# v0_1.net
KiCad netlist of a schematic drawn in EAGLE
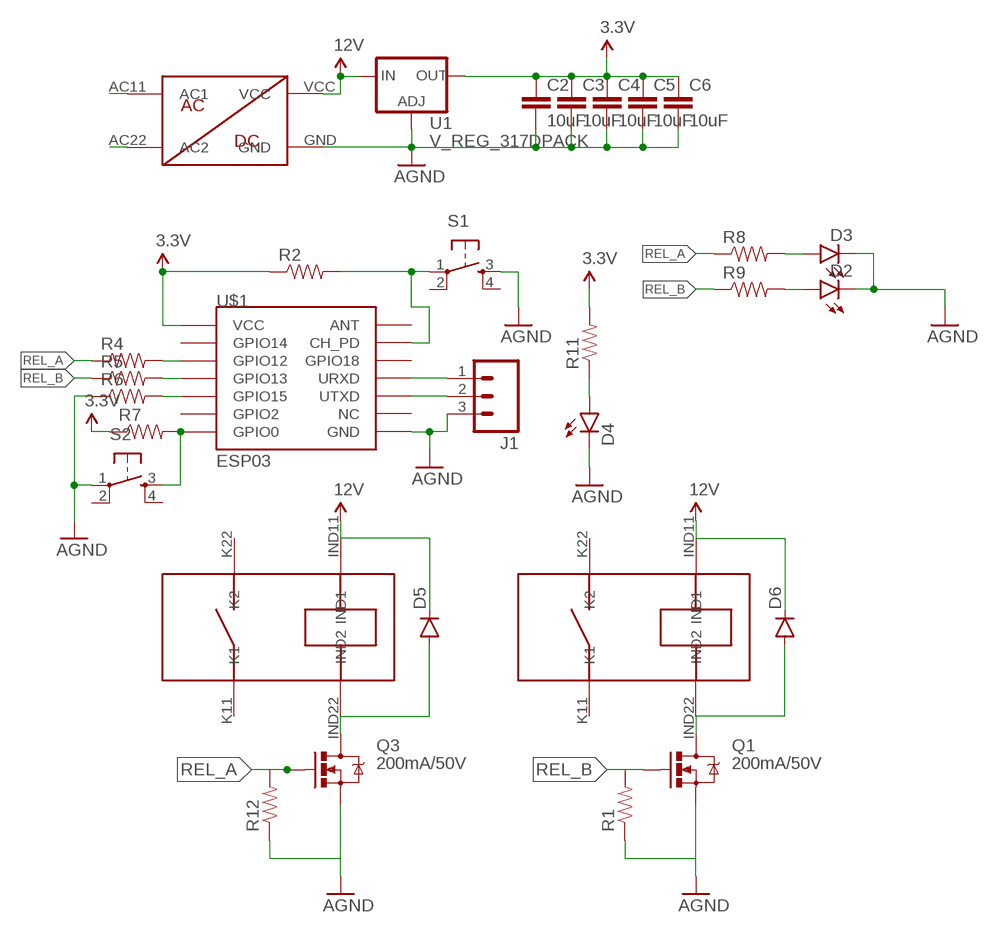
[diagram p0: schematic, sheet 1]

(export (version "E")
  (design (tool "Eeschema 10.0.6"))
  (components
    (comp (ref "C2")
      (value "10uF")
      (footprint "eagle-import:0603-CAP")
      (libsource (lib "eagle-import") (part "10UF-6.3V-20%(0603)"))
    )
    (comp (ref "C3")
      (value "10uF")
      (footprint "eagle-import:0603-CAP")
      (libsource (lib "eagle-import") (part "10UF-6.3V-20%(0603)"))
    )
    (comp (ref "C4")
      (value "10uF")
      (footprint "eagle-import:0603-CAP")
      (libsource (lib "eagle-import") (part "10UF-6.3V-20%(0603)"))
    )
    (comp (ref "C5")
      (value "10uF")
      (footprint "eagle-import:0603-CAP")
      (libsource (lib "eagle-import") (part "10UF-6.3V-20%(0603)"))
    )
    (comp (ref "C6")
      (value "10uF")
      (footprint "eagle-import:0603-CAP")
      (libsource (lib "eagle-import") (part "10UF-6.3V-20%(0603)"))
    )
    (comp (ref "D2")
      (value "LED0603")
      (footprint "eagle-import:LED-0603")
      (libsource (lib "eagle-import") (part "LED0603"))
    )
    (comp (ref "D3")
      (value "LED0603")
      (footprint "eagle-import:LED-0603")
      (libsource (lib "eagle-import") (part "LED0603"))
    )
    (comp (ref "D4")
      (value "LED0603")
      (footprint "eagle-import:LED-0603")
      (libsource (lib "eagle-import") (part "LED0603"))
    )
    (comp (ref "D5")
      (value "DIODESOD123")
      (footprint "eagle-import:SOD-123")
      (libsource (lib "eagle-import") (part "DIODESOD123"))
    )
    (comp (ref "D6")
      (value "DIODESOD123")
      (footprint "eagle-import:SOD-123")
      (libsource (lib "eagle-import") (part "DIODESOD123"))
    )
    (comp (ref "J1")
      (value "M03LONGPADS")
      (footprint "eagle-import:1X03_LONGPADS")
      (libsource (lib "eagle-import") (part "M03LONGPADS"))
    )
    (comp (ref "Q1")
      (value "200mA/50V")
      (footprint "eagle-import:SOT23-3")
      (libsource (lib "eagle-import") (part "MOSFET-NCHANNELBSS138"))
    )
    (comp (ref "Q3")
      (value "200mA/50V")
      (footprint "eagle-import:SOT23-3")
      (libsource (lib "eagle-import") (part "MOSFET-NCHANNELBSS138"))
    )
    (comp (ref "R1")
      (value "RESISTOR0805-RES")
      (footprint "eagle-import:0805")
      (libsource (lib "eagle-import") (part "RESISTOR0805-RES"))
    )
    (comp (ref "R2")
      (value "RESISTOR0805-RES")
      (footprint "eagle-import:0805")
      (libsource (lib "eagle-import") (part "RESISTOR0805-RES"))
    )
    (comp (ref "R4")
      (value "RESISTOR0805-RES")
      (footprint "eagle-import:0805")
      (libsource (lib "eagle-import") (part "RESISTOR0805-RES"))
    )
    (comp (ref "R5")
      (value "RESISTOR0805-RES")
      (footprint "eagle-import:0805")
      (libsource (lib "eagle-import") (part "RESISTOR0805-RES"))
    )
    (comp (ref "R6")
      (value "RESISTOR0805-RES")
      (footprint "eagle-import:0805")
      (libsource (lib "eagle-import") (part "RESISTOR0805-RES"))
    )
    (comp (ref "R7")
      (value "RESISTOR0805-RES")
      (footprint "eagle-import:0805")
      (libsource (lib "eagle-import") (part "RESISTOR0805-RES"))
    )
    (comp (ref "R8")
      (value "RESISTOR0805-RES")
      (footprint "eagle-import:0805")
      (libsource (lib "eagle-import") (part "RESISTOR0805-RES"))
    )
    (comp (ref "R9")
      (value "RESISTOR0805-RES")
      (footprint "eagle-import:0805")
      (libsource (lib "eagle-import") (part "RESISTOR0805-RES"))
    )
    (comp (ref "R11")
      (value "RESISTOR0805-RES")
      (footprint "eagle-import:0805")
      (libsource (lib "eagle-import") (part "RESISTOR0805-RES"))
    )
    (comp (ref "R12")
      (value "RESISTOR0805-RES")
      (footprint "eagle-import:0805")
      (libsource (lib "eagle-import") (part "RESISTOR0805-RES"))
    )
    (comp (ref "S1")
      (value "TAC_SWITCHPTH")
      (footprint "eagle-import:TACTILE-PTH")
      (libsource (lib "eagle-import") (part "TAC_SWITCHPTH"))
    )
    (comp (ref "S2")
      (value "TAC_SWITCHPTH")
      (footprint "eagle-import:TACTILE-PTH")
      (libsource (lib "eagle-import") (part "TAC_SWITCHPTH"))
    )
    (comp (ref "U$1")
      (value "ESP03")
      (footprint "eagle-import:ESP03")
      (libsource (lib "eagle-import") (part "ESP03"))
    )
    (comp (ref "U$8")
      (value "ACDC12V350MA")
      (footprint "eagle-import:ACDC12V350MA")
      (libsource (lib "eagle-import") (part "ACDC12V350MA"))
    )
    (comp (ref "U$9")
      (value "302WP")
      (footprint "eagle-import:302WP")
      (libsource (lib "eagle-import") (part "302WP"))
    )
    (comp (ref "U$10")
      (value "302WP")
      (footprint "eagle-import:302WP")
      (libsource (lib "eagle-import") (part "302WP"))
    )
    (comp (ref "U1")
      (value "V_REG_317DPACK")
      (footprint "eagle-import:V-REG_DPACK")
      (libsource (lib "eagle-import") (part "V_REG_317DPACK"))
    )
  )
  (nets
    (net (code "1") (name "3.3V") (class "Default")
      (node (ref "C2") (pin "1") (pinfunction "1_1") (pintype "passive"))
      (node (ref "C3") (pin "1") (pinfunction "1_1") (pintype "passive"))
      (node (ref "C4") (pin "1") (pinfunction "1_1") (pintype "passive"))
      (node (ref "C5") (pin "1") (pinfunction "1_1") (pintype "passive"))
      (node (ref "C6") (pin "1") (pinfunction "1_1") (pintype "passive"))
      (node (ref "R11") (pin "2") (pinfunction "2_2") (pintype "passive"))
      (node (ref "R2") (pin "1") (pinfunction "1_1") (pintype "passive"))
      (node (ref "R7") (pin "1") (pinfunction "1_1") (pintype "passive"))
      (node (ref "U$1") (pin "VCC") (pinfunction "VCC_VCC") (pintype "bidirectional"))
      (node (ref "U1") (pin "4") (pinfunction "OUT_4") (pintype "output"))
    )
    (net (code "2") (name "12V") (class "Default")
      (node (ref "D5") (pin "C") (pinfunction "C_C") (pintype "passive"))
      (node (ref "D6") (pin "C") (pinfunction "C_C") (pintype "passive"))
      (node (ref "U$10") (pin "IND11") (pinfunction "IND1_IND11") (pintype "bidirectional"))
      (node (ref "U$8") (pin "VCC") (pinfunction "VCC_VCC") (pintype "bidirectional"))
      (node (ref "U$9") (pin "IND11") (pinfunction "IND1_IND11") (pintype "bidirectional"))
      (node (ref "U1") (pin "3") (pinfunction "IN_3") (pintype "input"))
    )
    (net (code "3") (name "AGND") (class "Default")
      (node (ref "C2") (pin "2") (pinfunction "2_2") (pintype "passive"))
      (node (ref "C3") (pin "2") (pinfunction "2_2") (pintype "passive"))
      (node (ref "C4") (pin "2") (pinfunction "2_2") (pintype "passive"))
      (node (ref "C5") (pin "2") (pinfunction "2_2") (pintype "passive"))
      (node (ref "C6") (pin "2") (pinfunction "2_2") (pintype "passive"))
      (node (ref "D2") (pin "C") (pinfunction "C_C") (pintype "passive"))
      (node (ref "D3") (pin "C") (pinfunction "C_C") (pintype "passive"))
      (node (ref "D4") (pin "C") (pinfunction "C_C") (pintype "passive"))
      (node (ref "J1") (pin "3") (pinfunction "3_3") (pintype "passive"))
      (node (ref "Q1") (pin "2") (pinfunction "S_2") (pintype "passive"))
      (node (ref "Q3") (pin "2") (pinfunction "S_2") (pintype "passive"))
      (node (ref "R1") (pin "1") (pinfunction "1_1") (pintype "passive"))
      (node (ref "R12") (pin "1") (pinfunction "1_1") (pintype "passive"))
      (node (ref "R6") (pin "1") (pinfunction "1_1") (pintype "passive"))
      (node (ref "S1") (pin "3") (pinfunction "3_3") (pintype "passive"))
      (node (ref "S2") (pin "1") (pinfunction "1_1") (pintype "passive"))
      (node (ref "U$1") (pin "GND") (pinfunction "GND_GND") (pintype "bidirectional"))
      (node (ref "U$8") (pin "GND") (pinfunction "GND_GND") (pintype "bidirectional"))
      (node (ref "U1") (pin "1") (pinfunction "ADJ_1") (pintype "input"))
    )
    (net (code "4") (name "Net-(D2-PadA)") (class "Default")
      (node (ref "D2") (pin "A") (pinfunction "A_A") (pintype "passive"))
      (node (ref "R9") (pin "2") (pinfunction "2_2") (pintype "passive"))
    )
    (net (code "5") (name "Net-(D3-PadA)") (class "Default")
      (node (ref "D3") (pin "A") (pinfunction "A_A") (pintype "passive"))
      (node (ref "R8") (pin "2") (pinfunction "2_2") (pintype "passive"))
    )
    (net (code "6") (name "Net-(D4-PadA)") (class "Default")
      (node (ref "D4") (pin "A") (pinfunction "A_A") (pintype "passive"))
      (node (ref "R11") (pin "1") (pinfunction "1_1") (pintype "passive"))
    )
    (net (code "7") (name "Net-(J1-Pad1)") (class "Default")
      (node (ref "J1") (pin "1") (pinfunction "1_1") (pintype "passive"))
      (node (ref "U$1") (pin "URXD") (pinfunction "URXD_URXD") (pintype "bidirectional"))
    )
    (net (code "8") (name "Net-(J1-Pad2)") (class "Default")
      (node (ref "J1") (pin "2") (pinfunction "2_2") (pintype "passive"))
      (node (ref "U$1") (pin "UTXD") (pinfunction "UTXD_UTXD") (pintype "bidirectional"))
    )
    (net (code "9") (name "Net-(Q1-D)") (class "Default")
      (node (ref "D6") (pin "A") (pinfunction "A_A") (pintype "passive"))
      (node (ref "Q1") (pin "3") (pinfunction "D_3") (pintype "passive"))
      (node (ref "U$9") (pin "IND22") (pinfunction "IND2_IND22") (pintype "bidirectional"))
    )
    (net (code "10") (name "Net-(Q3-D)") (class "Default")
      (node (ref "D5") (pin "A") (pinfunction "A_A") (pintype "passive"))
      (node (ref "Q3") (pin "3") (pinfunction "D_3") (pintype "passive"))
      (node (ref "U$10") (pin "IND22") (pinfunction "IND2_IND22") (pintype "bidirectional"))
    )
    (net (code "11") (name "Net-(R2-Pad2)") (class "Default")
      (node (ref "R2") (pin "2") (pinfunction "2_2") (pintype "passive"))
      (node (ref "S1") (pin "1") (pinfunction "1_1") (pintype "passive"))
      (node (ref "U$1") (pin "CH_PD") (pinfunction "CH_PD_CH_PD") (pintype "bidirectional"))
    )
    (net (code "12") (name "Net-(R4-Pad2)") (class "Default")
      (node (ref "R4") (pin "2") (pinfunction "2_2") (pintype "passive"))
      (node (ref "U$1") (pin "GPIO12") (pinfunction "GPIO12_GPIO12") (pintype "bidirectional"))
    )
    (net (code "13") (name "Net-(R5-Pad2)") (class "Default")
      (node (ref "R5") (pin "2") (pinfunction "2_2") (pintype "passive"))
      (node (ref "U$1") (pin "GPIO13") (pinfunction "GPIO13_GPIO13") (pintype "bidirectional"))
    )
    (net (code "14") (name "Net-(R6-Pad2)") (class "Default")
      (node (ref "R6") (pin "2") (pinfunction "2_2") (pintype "passive"))
      (node (ref "U$1") (pin "GPIO15") (pinfunction "GPIO15_GPIO15") (pintype "bidirectional"))
    )
    (net (code "15") (name "Net-(R7-Pad2)") (class "Default")
      (node (ref "R7") (pin "2") (pinfunction "2_2") (pintype "passive"))
      (node (ref "S2") (pin "3") (pinfunction "3_3") (pintype "passive"))
      (node (ref "U$1") (pin "GPIO0") (pinfunction "GPIO0_GPIO0") (pintype "bidirectional"))
    )
    (net (code "16") (name "REL_A") (class "Default")
      (node (ref "Q3") (pin "1") (pinfunction "G_1") (pintype "passive"))
      (node (ref "R12") (pin "2") (pinfunction "2_2") (pintype "passive"))
      (node (ref "R4") (pin "1") (pinfunction "1_1") (pintype "passive"))
      (node (ref "R8") (pin "1") (pinfunction "1_1") (pintype "passive"))
    )
    (net (code "17") (name "REL_B") (class "Default")
      (node (ref "Q1") (pin "1") (pinfunction "G_1") (pintype "passive"))
      (node (ref "R1") (pin "2") (pinfunction "2_2") (pintype "passive"))
      (node (ref "R5") (pin "1") (pinfunction "1_1") (pintype "passive"))
      (node (ref "R9") (pin "1") (pinfunction "1_1") (pintype "passive"))
    )
    (net (code "18") (name "unconnected-(S1-Pad2)") (class "Default")
      (node (ref "S1") (pin "2") (pinfunction "2_2") (pintype "passive"))
    )
    (net (code "19") (name "unconnected-(S1-Pad4)") (class "Default")
      (node (ref "S1") (pin "4") (pinfunction "4_4") (pintype "passive"))
    )
    (net (code "20") (name "unconnected-(S2-Pad2)") (class "Default")
      (node (ref "S2") (pin "2") (pinfunction "2_2") (pintype "passive"))
    )
    (net (code "21") (name "unconnected-(S2-Pad4)") (class "Default")
      (node (ref "S2") (pin "4") (pinfunction "4_4") (pintype "passive"))
    )
    (net (code "22") (name "unconnected-(U$1-PadANT)") (class "Default")
      (node (ref "U$1") (pin "ANT") (pinfunction "ANT_ANT") (pintype "bidirectional"))
    )
    (net (code "23") (name "unconnected-(U$1-PadGPIO2)") (class "Default")
      (node (ref "U$1") (pin "GPIO2") (pinfunction "GPIO2_GPIO2") (pintype "bidirectional"))
    )
    (net (code "24") (name "unconnected-(U$1-PadGPIO14)") (class "Default")
      (node (ref "U$1") (pin "GPIO14") (pinfunction "GPIO14_GPIO14") (pintype "bidirectional"))
    )
    (net (code "25") (name "unconnected-(U$1-PadGPIO18)") (class "Default")
      (node (ref "U$1") (pin "GPIO18") (pinfunction "GPIO18_GPIO18") (pintype "bidirectional"))
    )
    (net (code "26") (name "unconnected-(U$1-PadNC)") (class "Default")
      (node (ref "U$1") (pin "NC") (pinfunction "NC_NC") (pintype "bidirectional"))
    )
    (net (code "27") (name "unconnected-(U$8-AC1-PadAC11)") (class "Default")
      (node (ref "U$8") (pin "AC11") (pinfunction "AC1_AC11") (pintype "bidirectional"))
    )
    (net (code "28") (name "unconnected-(U$8-AC2-PadAC22)") (class "Default")
      (node (ref "U$8") (pin "AC22") (pinfunction "AC2_AC22") (pintype "bidirectional"))
    )
    (net (code "29") (name "unconnected-(U$9-K1-PadK11)") (class "Default")
      (node (ref "U$9") (pin "K11") (pinfunction "K1_K11") (pintype "bidirectional"))
    )
    (net (code "30") (name "unconnected-(U$9-K2-PadK22)") (class "Default")
      (node (ref "U$9") (pin "K22") (pinfunction "K2_K22") (pintype "bidirectional"))
    )
    (net (code "31") (name "unconnected-(U$10-K1-PadK11)") (class "Default")
      (node (ref "U$10") (pin "K11") (pinfunction "K1_K11") (pintype "bidirectional"))
    )
    (net (code "32") (name "unconnected-(U$10-K2-PadK22)") (class "Default")
      (node (ref "U$10") (pin "K22") (pinfunction "K2_K22") (pintype "bidirectional"))
    )
  )
)
